# Grove_-_Infrared_Reflective_Sensor.net
KiCad netlist of a schematic drawn in EAGLE
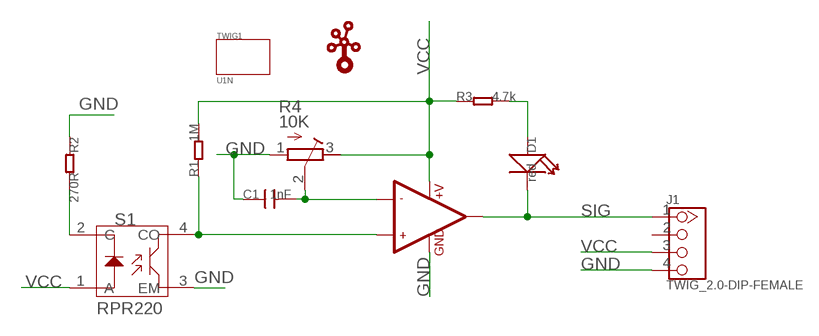
[diagram p0: schematic, sheet 1]

(export (version "E")
  (design (tool "Eeschema 10.0.6"))
  (components
    (comp (ref "C1")
      (value "1nF")
      (footprint "eagle-import:0603")
      (libsource (lib "eagle-import") (part "C-0603"))
    )
    (comp (ref "D1")
      (value "red")
      (footprint "eagle-import:LED0603")
      (libsource (lib "eagle-import") (part "007-LED3540"))
    )
    (comp (ref "J1")
      (value "TWIG_2.0-DIP-FEMALE")
      (footprint "eagle-import:2.0_1X4")
      (libsource (lib "eagle-import") (part "TWIG_2.0-DIP-FEMALE"))
    )
    (comp (ref "R1")
      (value "1M")
      (footprint "eagle-import:0603_S")
      (libsource (lib "eagle-import") (part "005-R0603_S"))
    )
    (comp (ref "R2")
      (value "270R")
      (footprint "eagle-import:0603_S")
      (libsource (lib "eagle-import") (part "005-R0603_S"))
    )
    (comp (ref "R3")
      (value "4.7k")
      (footprint "eagle-import:0603_S")
      (libsource (lib "eagle-import") (part "005-R0603_S"))
    )
    (comp (ref "R4")
      (value "10K")
      (footprint "eagle-import:RTRIM3214W")
      (libsource (lib "eagle-import") (part "R-TRIMM3214W"))
    )
    (comp (ref "S1")
      (value "RPR220")
      (footprint "eagle-import:4P-6.4X4.9X6.5H")
      (libsource (lib "eagle-import") (part "REFLECTIVE-PHOTOSENSOR-RPR-220"))
    )
    (comp (ref "TWIG1")
      (value "U1N")
      (footprint "eagle-import:U1N")
      (libsource (lib "eagle-import") (part "U1N"))
    )
    (comp (ref "U$2")
      (value "TWIGLOGOTWIGLOGO_SMALL")
      (footprint "eagle-import:TWIGLOGO_SMALL")
      (libsource (lib "eagle-import") (part "TWIGLOGOTWIGLOGO_SMALL"))
    )
    (comp (ref "U1")
      (value "002-LMV358")
      (footprint "eagle-import:SO08")
      (libsource (lib "eagle-import") (part "002-LMV358"))
    )
  )
  (nets
    (net (code "1") (name "/GND") (class "Default")
      (node (ref "C1") (pin "1") (pinfunction "1_1") (pintype "passive"))
      (node (ref "J1") (pin "4") (pinfunction "4_4") (pintype "bidirectional"))
      (node (ref "R2") (pin "1") (pinfunction "1_1") (pintype "passive"))
      (node (ref "R4") (pin "1") (pinfunction "E_1") (pintype "passive"))
      (node (ref "S1") (pin "3") (pinfunction "EM_3") (pintype "bidirectional"))
      (node (ref "U1") (pin "4") (pinfunction "GND_4") (pintype "power_in"))
    )
    (net (code "2") (name "/SIG") (class "Default")
      (node (ref "D1") (pin "2") (pinfunction "-_2") (pintype "passive"))
      (node (ref "J1") (pin "1") (pinfunction "1_1") (pintype "bidirectional"))
      (node (ref "U1") (pin "1") (pinfunction "OUT1_1") (pintype "output"))
    )
    (net (code "3") (name "/VCC") (class "Default")
      (node (ref "J1") (pin "3") (pinfunction "3_3") (pintype "bidirectional"))
      (node (ref "R1") (pin "2") (pinfunction "2_2") (pintype "passive"))
      (node (ref "R3") (pin "1") (pinfunction "1_1") (pintype "passive"))
      (node (ref "R4") (pin "3") (pinfunction "A_3") (pintype "passive"))
      (node (ref "S1") (pin "1") (pinfunction "A_1") (pintype "bidirectional"))
      (node (ref "U1") (pin "8") (pinfunction "+V_8") (pintype "power_in"))
    )
    (net (code "4") (name "Net-(D1-+)") (class "Default")
      (node (ref "D1") (pin "1") (pinfunction "+_1") (pintype "passive"))
      (node (ref "R3") (pin "2") (pinfunction "2_2") (pintype "passive"))
    )
    (net (code "5") (name "Net-(R4-S)") (class "Default")
      (node (ref "C1") (pin "2") (pinfunction "2_2") (pintype "passive"))
      (node (ref "R4") (pin "2") (pinfunction "S_2") (pintype "passive"))
      (node (ref "U1") (pin "2") (pinfunction "-IN1_2") (pintype "input"))
    )
    (net (code "6") (name "Net-(S1-C)") (class "Default")
      (node (ref "R2") (pin "2") (pinfunction "2_2") (pintype "passive"))
      (node (ref "S1") (pin "2") (pinfunction "C_2") (pintype "bidirectional"))
    )
    (net (code "7") (name "Net-(S1-CO)") (class "Default")
      (node (ref "R1") (pin "1") (pinfunction "1_1") (pintype "passive"))
      (node (ref "S1") (pin "4") (pinfunction "CO_4") (pintype "bidirectional"))
      (node (ref "U1") (pin "3") (pinfunction "+IN1_3") (pintype "input"))
    )
    (net (code "8") (name "unconnected-(J1-Pad2)") (class "Default")
      (node (ref "J1") (pin "2") (pinfunction "2_2") (pintype "bidirectional"))
    )
  )
)
